# schematics.net
KiCad netlist of a schematic drawn in EasyEDA
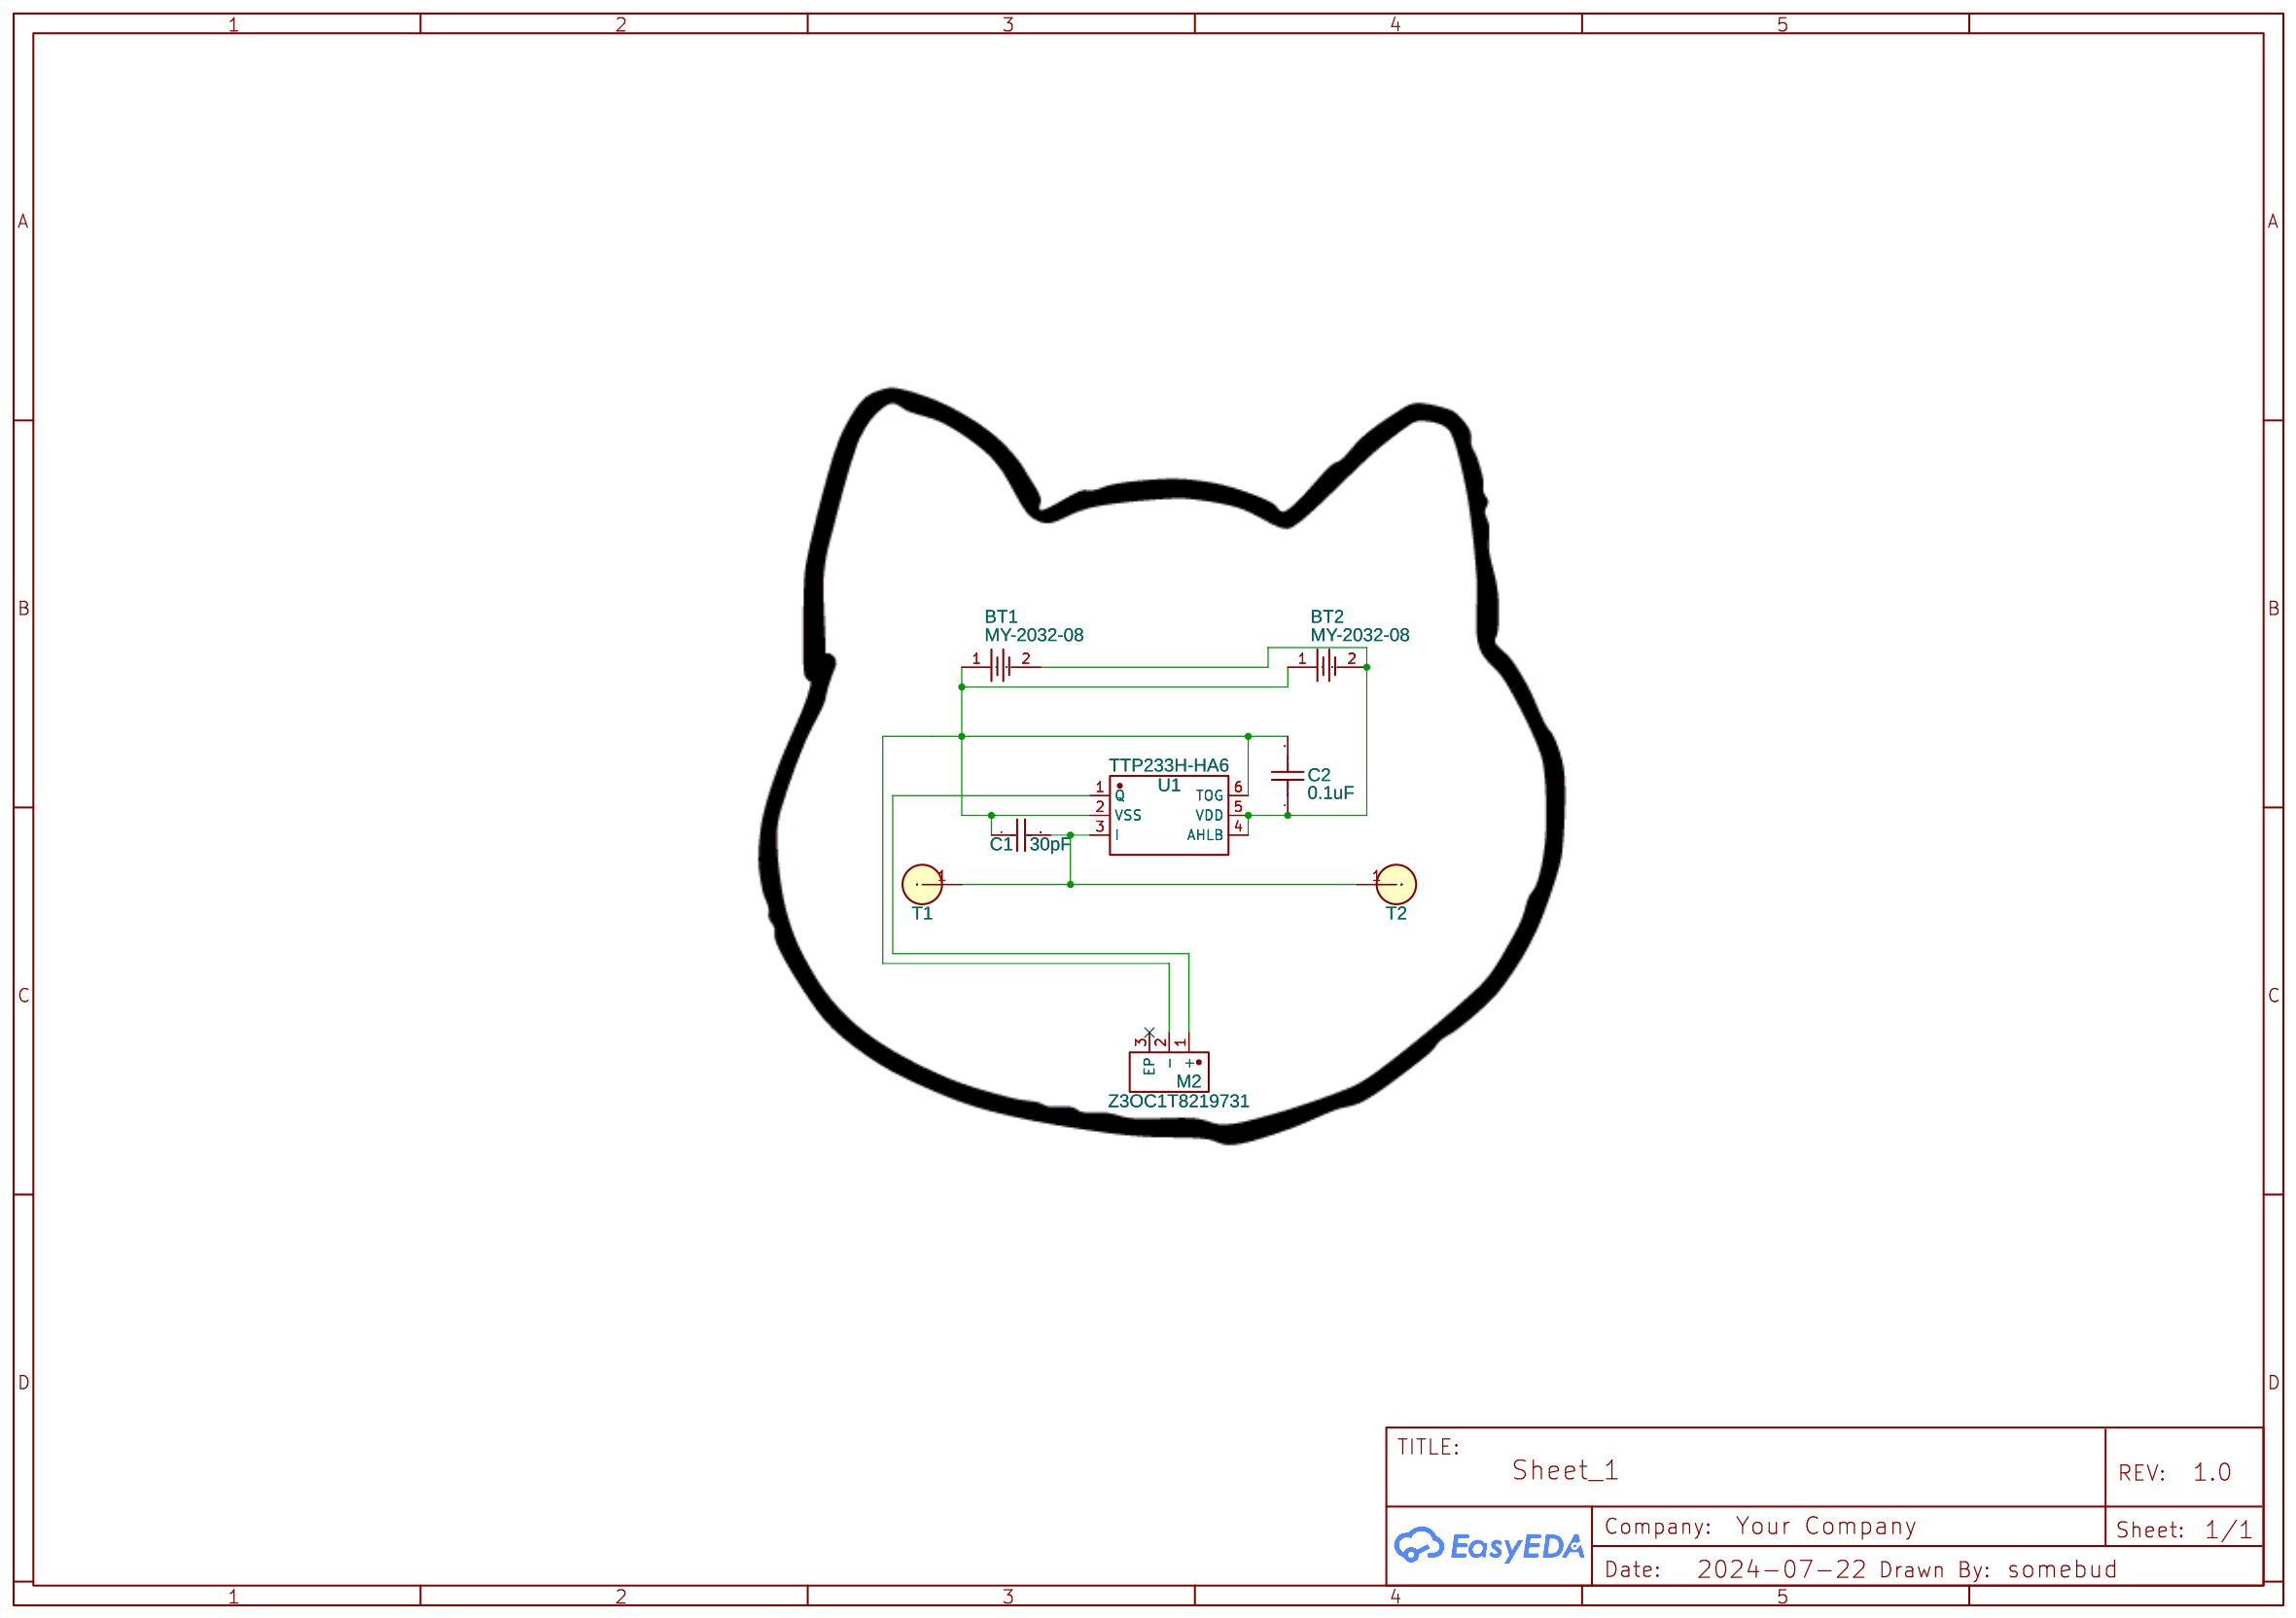
[diagram p0: schematic sheet]

(export (version "E")
  (design (tool "Eeschema 10.0.6"))
  (components
    (comp (ref "BT1")
      (value "MY-2032-08")
      (fields (field (name "Manufacturer") "MYOUNG(美阳)"))
      (libsource (lib "") (part "MY-2032-08"))
    )
    (comp (ref "BT2")
      (value "MY-2032-08")
      (fields (field (name "Manufacturer") "MYOUNG(美阳)"))
      (libsource (lib "") (part "MY-2032-08"))
    )
    (comp (ref "C1")
      (value "30pF")
      (fields (field (name "Manufacturer Part") "0603CG300J500NT") (field (name "Manufacturer") "FH(风华)"))
      (libsource (lib "") (part "0603CG300J500NT"))
    )
    (comp (ref "C2") (value "0.1uF") (libsource (lib "") (part "C_0603_US")))
    (comp (ref "M2")
      (value "Z3OC1T8219731")
      (fields (field (name "Manufacturer") "KOTL(金龙机电)"))
      (libsource (lib "") (part "Z3OC1T8219731"))
    )
    (comp (ref "T1")
      (value "TOUCHPAD 12mm circle nopaste nomask")
      (libsource (lib "") (part "TOUCHPAD 12mm circle nopaste nomask_1"))
    )
    (comp (ref "T2")
      (value "TOUCHPAD 12mm circle nopaste nomask")
      (libsource (lib "") (part "TOUCHPAD 12mm circle nopaste nomask"))
    )
    (comp (ref "U1")
      (value "TTP233H-HA6")
      (fields (field (name "Manufacturer") "TONTEK(通泰)"))
      (libsource (lib "") (part "TTP233H-HA6"))
    )
  )
  (nets
    (net (code "1") (name "Net-(M2-+)") (class "Default")
      (node (ref "M2") (pin "1") (pinfunction "+_1") (pintype "unspecified"))
      (node (ref "U1") (pin "1") (pinfunction "Q_1") (pintype "unspecified"))
    )
    (net (code "2") (name "Net-(M2--)") (class "Default")
      (node (ref "BT1") (pin "1") (pinfunction "1_1") (pintype "input"))
      (node (ref "BT2") (pin "1") (pinfunction "1_1") (pintype "input"))
      (node (ref "C1") (pin "1") (pinfunction "1_1") (pintype "input"))
      (node (ref "C2") (pin "2") (pinfunction "2_2") (pintype "unspecified"))
      (node (ref "M2") (pin "2") (pinfunction "-_2") (pintype "unspecified"))
      (node (ref "U1") (pin "2") (pinfunction "VSS_2") (pintype "unspecified"))
      (node (ref "U1") (pin "6") (pinfunction "TOG_6") (pintype "unspecified"))
    )
    (net (code "3") (name "Net-(T1-Touch)") (class "Default")
      (node (ref "C1") (pin "2") (pinfunction "2_2") (pintype "input"))
      (node (ref "T1") (pin "1") (pinfunction "Touch_1") (pintype "unspecified"))
      (node (ref "T2") (pin "1") (pinfunction "Touch_1") (pintype "unspecified"))
      (node (ref "U1") (pin "3") (pinfunction "I_3") (pintype "unspecified"))
    )
    (net (code "4") (name "Net-(U1-AHLB)") (class "Default")
      (node (ref "BT1") (pin "2") (pinfunction "2_2") (pintype "input"))
      (node (ref "BT2") (pin "2") (pinfunction "2_2") (pintype "input"))
      (node (ref "C2") (pin "1") (pinfunction "1_1") (pintype "unspecified"))
      (node (ref "U1") (pin "4") (pinfunction "AHLB_4") (pintype "unspecified"))
      (node (ref "U1") (pin "5") (pinfunction "VDD_5") (pintype "unspecified"))
    )
    (net (code "5") (name "unconnected-(M2-EP-Pad3)") (class "Default")
      (node (ref "M2") (pin "3") (pinfunction "EP_3") (pintype "unspecified+no_connect"))
    )
  )
)
